# 04_MOSFET.net
KiCad netlist of a schematic drawn in Altium Designer
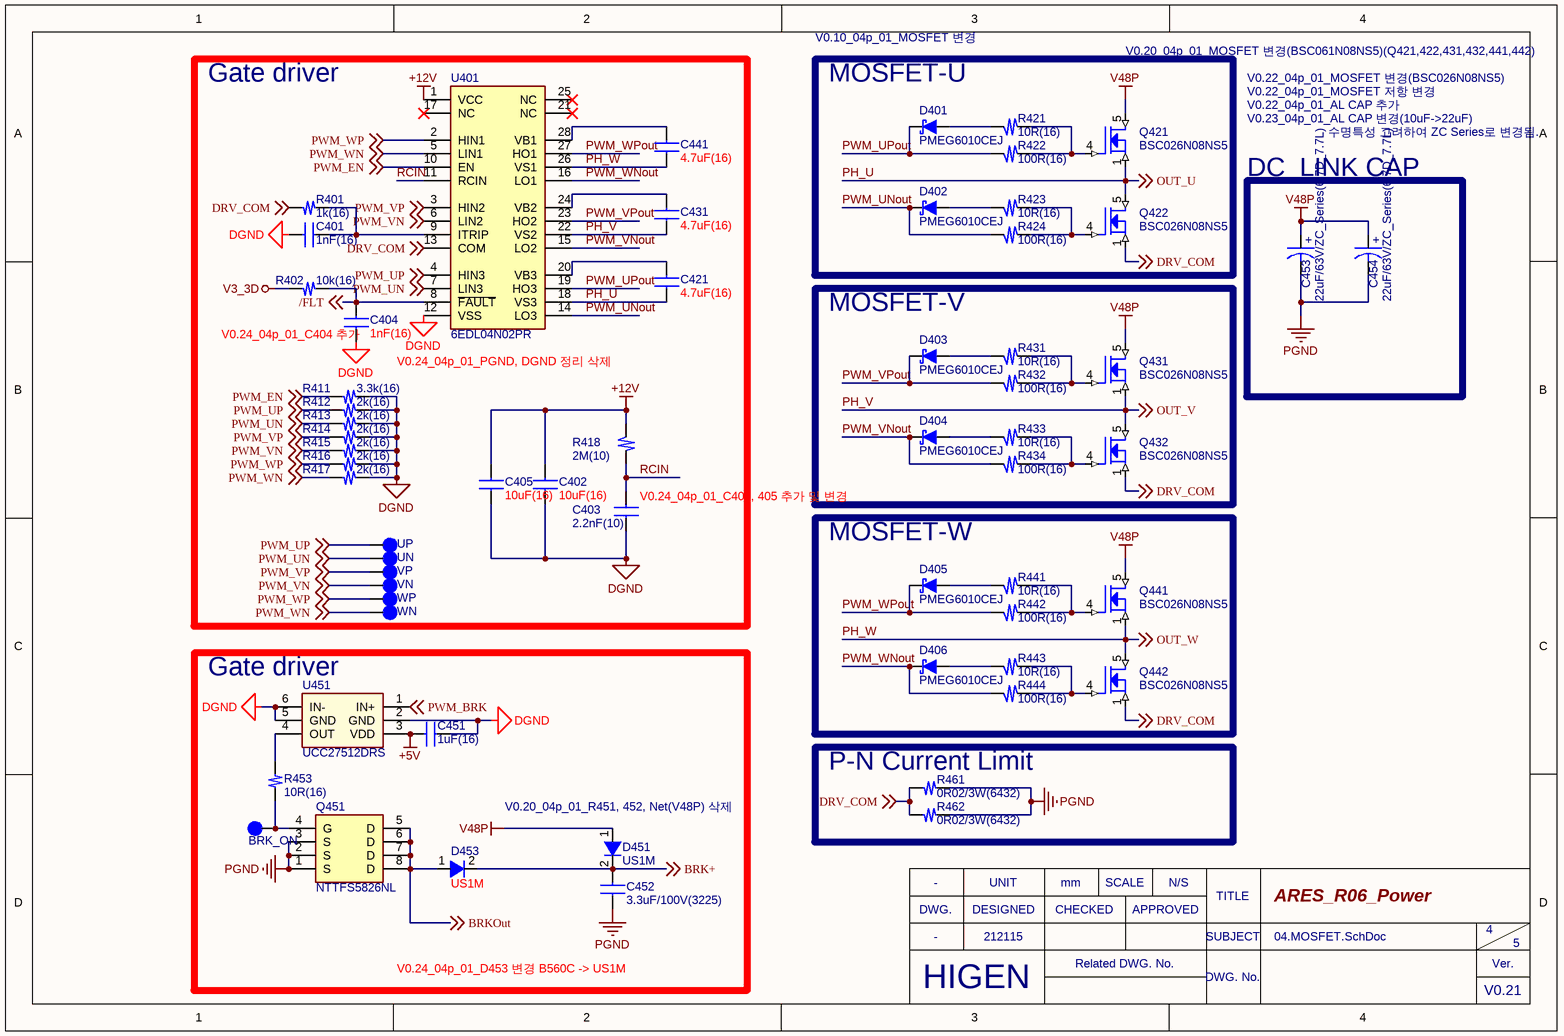
[diagram p0: 04.MOSFET.SchDoc]

(export (version "E")
  (design (tool "Eeschema 10.0.6"))
  (components
    (comp (ref "BRK_ON")
      (value "TP")
      (footprint "TP-SMD")
      (fields (field (name "MFR") "Keystone Electronics") (field (name "TIINTPARTNUMBER") "2H0026"))
      (libsource (lib "*") (part "2H_TestPointThroughHole"))
    )
    (comp (ref "C401")
      (value "1nF(16)")
      (footprint "C-1608S")
      (libsource (lib "AM437X_MAIN_LOW") (part "Cap_NP"))
    )
    (comp (ref "C402") (value "10uF(16)") (footprint "C-1608S") (libsource (lib "HIGEN") (part "Cap_NP")))
    (comp (ref "C403") (value "2.2nF(10)") (footprint "C-1005S") (libsource (lib "HIGEN") (part "Cap_NP")))
    (comp (ref "C404")
      (value "1nF(16)")
      (footprint "C-1608S")
      (libsource (lib "AM437X_MAIN_LOW") (part "Cap_NP"))
    )
    (comp (ref "C405") (value "10uF(16)") (footprint "C-1608S") (libsource (lib "HIGEN") (part "Cap_NP")))
    (comp (ref "C421") (value "4.7uF(16)") (footprint "C-1608S") (libsource (lib "HIGEN") (part "Cap_NP")))
    (comp (ref "C431") (value "4.7uF(16)") (footprint "C-1608S") (libsource (lib "HIGEN") (part "Cap_NP")))
    (comp (ref "C441") (value "4.7uF(16)") (footprint "C-1608S") (libsource (lib "HIGEN") (part "Cap_NP")))
    (comp (ref "C451")
      (value "1uF(16)")
      (footprint "C-1608S")
      (libsource (lib "AM437X_MAIN_LOW") (part "Cap_NP"))
    )
    (comp (ref "C452")
      (value "3.3uF/100V(3225)")
      (footprint "C-3225")
      (libsource (lib "HIGEN") (part "Cap_NP"))
    )
    (comp (ref "C453")
      (value "22uF/63V/ZC_Series(6.7D_7.7L)")
      (footprint "EC-F80")
      (libsource (lib "HIGEN") (part "CAP_Pol"))
    )
    (comp (ref "C454")
      (value "22uF/63V/ZC_Series(6.7D_7.7L)")
      (footprint "EC-F80")
      (libsource (lib "HIGEN") (part "CAP_Pol"))
    )
    (comp (ref "D401")
      (value "PMEG6010CEJ")
      (footprint "SOD-323")
      (libsource (lib "HIGEN") (part "Diode_schottky"))
    )
    (comp (ref "D402")
      (value "PMEG6010CEJ")
      (footprint "SOD-323")
      (libsource (lib "HIGEN") (part "Diode_schottky"))
    )
    (comp (ref "D403")
      (value "PMEG6010CEJ")
      (footprint "SOD-323")
      (libsource (lib "HIGEN") (part "Diode_schottky"))
    )
    (comp (ref "D404")
      (value "PMEG6010CEJ")
      (footprint "SOD-323")
      (libsource (lib "HIGEN") (part "Diode_schottky"))
    )
    (comp (ref "D405")
      (value "PMEG6010CEJ")
      (footprint "SOD-323")
      (libsource (lib "HIGEN") (part "Diode_schottky"))
    )
    (comp (ref "D406")
      (value "PMEG6010CEJ")
      (footprint "SOD-323")
      (libsource (lib "HIGEN") (part "Diode_schottky"))
    )
    (comp (ref "D451") (value "US1M") (footprint "SMA") (libsource (lib "HIGEN") (part "Diode")))
    (comp (ref "D453") (value "US1M") (footprint "SMA") (libsource (lib "HIGEN") (part "Diode")))
    (comp (ref "Q421")
      (value "BSC026N08NS5")
      (footprint "PG-TDSON-8 FL")
      (libsource (lib "*") (part "MOSFET N"))
    )
    (comp (ref "Q422")
      (value "BSC026N08NS5")
      (footprint "PG-TDSON-8 FL")
      (libsource (lib "*") (part "MOSFET N"))
    )
    (comp (ref "Q431")
      (value "BSC026N08NS5")
      (footprint "PG-TDSON-8 FL")
      (libsource (lib "*") (part "MOSFET N"))
    )
    (comp (ref "Q432")
      (value "BSC026N08NS5")
      (footprint "PG-TDSON-8 FL")
      (libsource (lib "*") (part "MOSFET N"))
    )
    (comp (ref "Q441")
      (value "BSC026N08NS5")
      (footprint "PG-TDSON-8 FL")
      (libsource (lib "*") (part "MOSFET N"))
    )
    (comp (ref "Q442")
      (value "BSC026N08NS5")
      (footprint "PG-TDSON-8 FL")
      (libsource (lib "*") (part "MOSFET N"))
    )
    (comp (ref "Q451")
      (value "NTTFS5826NL")
      (footprint "WDFN-8")
      (libsource (lib "HIGEN") (part "NTTFS5826NL"))
    )
    (comp (ref "R401") (value "1k(16)") (footprint "R-1608") (libsource (lib "HIGEN") (part "Res")))
    (comp (ref "R402") (value "10k(16)") (footprint "R-1608S") (libsource (lib "HIGEN") (part "Res")))
    (comp (ref "R411") (value "3.3k(16)") (footprint "R-1608S") (libsource (lib "HIGEN") (part "Res")))
    (comp (ref "R412") (value "2k(16)") (footprint "R-1608S") (libsource (lib "HIGEN") (part "Res")))
    (comp (ref "R413") (value "2k(16)") (footprint "R-1608S") (libsource (lib "HIGEN") (part "Res")))
    (comp (ref "R414") (value "2k(16)") (footprint "R-1608S") (libsource (lib "HIGEN") (part "Res")))
    (comp (ref "R415") (value "2k(16)") (footprint "R-1608S") (libsource (lib "HIGEN") (part "Res")))
    (comp (ref "R416") (value "2k(16)") (footprint "R-1608S") (libsource (lib "HIGEN") (part "Res")))
    (comp (ref "R417") (value "2k(16)") (footprint "R-1608S") (libsource (lib "HIGEN") (part "Res")))
    (comp (ref "R418")
      (value "2M(10)")
      (footprint "R-1005S")
      (libsource (lib "AM437X_MAIN_LOW") (part "Res"))
    )
    (comp (ref "R421") (value "10R(16)") (footprint "R-1608S") (libsource (lib "") (part "Res_1")))
    (comp (ref "R422") (value "100R(16)") (footprint "R-1608S") (libsource (lib "") (part "Res_1")))
    (comp (ref "R423") (value "10R(16)") (footprint "R-1608S") (libsource (lib "") (part "Res_1")))
    (comp (ref "R424") (value "100R(16)") (footprint "R-1608S") (libsource (lib "") (part "Res_1")))
    (comp (ref "R431") (value "10R(16)") (footprint "R-1608S") (libsource (lib "") (part "Res_1")))
    (comp (ref "R432") (value "100R(16)") (footprint "R-1608S") (libsource (lib "") (part "Res_1")))
    (comp (ref "R433") (value "10R(16)") (footprint "R-1608S") (libsource (lib "") (part "Res_1")))
    (comp (ref "R434") (value "100R(16)") (footprint "R-1608S") (libsource (lib "") (part "Res_1")))
    (comp (ref "R441") (value "10R(16)") (footprint "R-1608S") (libsource (lib "") (part "Res_1")))
    (comp (ref "R442") (value "100R(16)") (footprint "R-1608S") (libsource (lib "") (part "Res_1")))
    (comp (ref "R443") (value "10R(16)") (footprint "R-1608S") (libsource (lib "") (part "Res_1")))
    (comp (ref "R444") (value "100R(16)") (footprint "R-1608S") (libsource (lib "") (part "Res_1")))
    (comp (ref "R453") (value "10R(16)") (footprint "R-1608S") (libsource (lib "HIGEN") (part "Res")))
    (comp (ref "R461") (value "0R02/3W(6432)") (footprint "R-6432") (libsource (lib "HIGEN") (part "Res")))
    (comp (ref "R462") (value "0R02/3W(6432)") (footprint "R-6432") (libsource (lib "HIGEN") (part "Res")))
    (comp (ref "U401")
      (value "6EDL04N02PR")
      (footprint "TSSOP-28")
      (libsource (lib "HIGEN") (part "6EDL04N02PR"))
    )
    (comp (ref "U451")
      (value "UCC27512DRS")
      (footprint "WSON-6")
      (libsource (lib "HIGEN") (part "UCC27512DRS"))
    )
    (comp (ref "UN")
      (value "TP")
      (footprint "TP-SMD")
      (fields (field (name "MFR") "Keystone Electronics") (field (name "TIINTPARTNUMBER") "2H0026"))
      (libsource (lib "*") (part "2H_TestPointThroughHole"))
    )
    (comp (ref "UP")
      (value "TP")
      (footprint "TP-SMD")
      (fields (field (name "MFR") "Keystone Electronics") (field (name "TIINTPARTNUMBER") "2H0026"))
      (libsource (lib "*") (part "2H_TestPointThroughHole"))
    )
    (comp (ref "VN")
      (value "TP")
      (footprint "TP-SMD")
      (fields (field (name "MFR") "Keystone Electronics") (field (name "TIINTPARTNUMBER") "2H0026"))
      (libsource (lib "*") (part "2H_TestPointThroughHole"))
    )
    (comp (ref "VP")
      (value "TP")
      (footprint "TP-SMD")
      (fields (field (name "MFR") "Keystone Electronics") (field (name "TIINTPARTNUMBER") "2H0026"))
      (libsource (lib "*") (part "2H_TestPointThroughHole"))
    )
    (comp (ref "WN")
      (value "TP")
      (footprint "TP-SMD")
      (fields (field (name "MFR") "Keystone Electronics") (field (name "TIINTPARTNUMBER") "2H0026"))
      (libsource (lib "*") (part "2H_TestPointThroughHole"))
    )
    (comp (ref "WP")
      (value "TP")
      (footprint "TP-SMD")
      (fields (field (name "MFR") "Keystone Electronics") (field (name "TIINTPARTNUMBER") "2H0026"))
      (libsource (lib "*") (part "2H_TestPointThroughHole"))
    )
  )
  (nets
    (net (code "1") (name "+5V") (class "Default")
      (node (ref "C451") (pin "1") (pinfunction "1_1") (pintype "passive"))
      (node (ref "U451") (pin "3") (pinfunction "VDD_3") (pintype "passive"))
    )
    (net (code "2") (name "+12V") (class "Default")
      (node (ref "C402") (pin "1") (pinfunction "1_1") (pintype "passive"))
      (node (ref "C405") (pin "1") (pinfunction "1_1") (pintype "passive"))
      (node (ref "R418") (pin "2") (pinfunction "2_2") (pintype "passive"))
      (node (ref "U401") (pin "1") (pinfunction "VCC_1") (pintype "passive"))
    )
    (net (code "3") (name "/PWM_UNout") (class "Default")
      (node (ref "D402") (pin "2") (pinfunction "K_2") (pintype "passive"))
      (node (ref "R424") (pin "2") (pinfunction "2_2") (pintype "passive"))
      (node (ref "U401") (pin "14") (pinfunction "LO3_14") (pintype "passive"))
    )
    (net (code "4") (name "/PWM_UPout") (class "Default")
      (node (ref "D401") (pin "2") (pinfunction "K_2") (pintype "passive"))
      (node (ref "R422") (pin "2") (pinfunction "2_2") (pintype "passive"))
      (node (ref "U401") (pin "19") (pinfunction "HO3_19") (pintype "passive"))
    )
    (net (code "5") (name "/PWM_VNout") (class "Default")
      (node (ref "D404") (pin "2") (pinfunction "K_2") (pintype "passive"))
      (node (ref "R434") (pin "2") (pinfunction "2_2") (pintype "passive"))
      (node (ref "U401") (pin "15") (pinfunction "LO2_15") (pintype "passive"))
    )
    (net (code "6") (name "/PWM_VPout") (class "Default")
      (node (ref "D403") (pin "2") (pinfunction "K_2") (pintype "passive"))
      (node (ref "R432") (pin "2") (pinfunction "2_2") (pintype "passive"))
      (node (ref "U401") (pin "23") (pinfunction "HO2_23") (pintype "passive"))
    )
    (net (code "7") (name "/PWM_WNout") (class "Default")
      (node (ref "D406") (pin "2") (pinfunction "K_2") (pintype "passive"))
      (node (ref "R444") (pin "2") (pinfunction "2_2") (pintype "passive"))
      (node (ref "U401") (pin "16") (pinfunction "LO1_16") (pintype "passive"))
    )
    (net (code "8") (name "/PWM_WPout") (class "Default")
      (node (ref "D405") (pin "2") (pinfunction "K_2") (pintype "passive"))
      (node (ref "R442") (pin "2") (pinfunction "2_2") (pintype "passive"))
      (node (ref "U401") (pin "27") (pinfunction "HO1_27") (pintype "passive"))
    )
    (net (code "9") (name "/RCIN") (class "Default")
      (node (ref "C403") (pin "2") (pinfunction "2_2") (pintype "passive"))
      (node (ref "R418") (pin "1") (pinfunction "1_1") (pintype "passive"))
      (node (ref "U401") (pin "11") (pinfunction "RCIN_11") (pintype "passive"))
    )
    (net (code "10") (name "BRK+") (class "Default")
      (node (ref "C452") (pin "2") (pinfunction "2_2") (pintype "passive"))
      (node (ref "D451") (pin "2") (pinfunction "K_2") (pintype "passive"))
      (node (ref "D453") (pin "2") (pinfunction "K_2") (pintype "passive"))
    )
    (net (code "11") (name "BRKOut") (class "Default")
      (node (ref "D453") (pin "1") (pinfunction "A_1") (pintype "passive"))
      (node (ref "Q451") (pin "5") (pinfunction "D_5") (pintype "passive"))
      (node (ref "Q451") (pin "6") (pinfunction "D_6") (pintype "passive"))
      (node (ref "Q451") (pin "7") (pinfunction "D_7") (pintype "passive"))
      (node (ref "Q451") (pin "8") (pinfunction "D_8") (pintype "passive"))
    )
    (net (code "12") (name "DGND") (class "Default")
      (node (ref "C401") (pin "1") (pinfunction "1_1") (pintype "passive"))
      (node (ref "C402") (pin "2") (pinfunction "2_2") (pintype "passive"))
      (node (ref "C403") (pin "1") (pinfunction "1_1") (pintype "passive"))
      (node (ref "C404") (pin "1") (pinfunction "1_1") (pintype "passive"))
      (node (ref "C405") (pin "2") (pinfunction "2_2") (pintype "passive"))
      (node (ref "C451") (pin "2") (pinfunction "2_2") (pintype "passive"))
      (node (ref "R411") (pin "2") (pinfunction "P2_2") (pintype "passive"))
      (node (ref "R412") (pin "1") (pinfunction "P1_1") (pintype "passive"))
      (node (ref "R413") (pin "1") (pinfunction "P1_1") (pintype "passive"))
      (node (ref "R414") (pin "1") (pinfunction "P1_1") (pintype "passive"))
      (node (ref "R415") (pin "1") (pinfunction "P1_1") (pintype "passive"))
      (node (ref "R416") (pin "2") (pinfunction "P2_2") (pintype "passive"))
      (node (ref "R417") (pin "2") (pinfunction "P2_2") (pintype "passive"))
      (node (ref "U401") (pin "12") (pinfunction "VSS_12") (pintype "passive"))
      (node (ref "U451") (pin "2") (pinfunction "GND_2") (pintype "passive"))
      (node (ref "U451") (pin "5") (pinfunction "GND_5") (pintype "passive"))
      (node (ref "U451") (pin "6") (pinfunction "IN-_6") (pintype "passive"))
    )
    (net (code "13") (name "DRV_COM") (class "Default")
      (node (ref "Q422") (pin "1") (pinfunction "SOURCE_1") (pintype "input"))
      (node (ref "Q432") (pin "1") (pinfunction "SOURCE_1") (pintype "input"))
      (node (ref "Q442") (pin "1") (pinfunction "SOURCE_1") (pintype "input"))
      (node (ref "R401") (pin "1") (pinfunction "P1_1") (pintype "passive"))
      (node (ref "R461") (pin "2") (pinfunction "P2_2") (pintype "passive"))
      (node (ref "R462") (pin "2") (pinfunction "P2_2") (pintype "passive"))
      (node (ref "U401") (pin "13") (pinfunction "COM_13") (pintype "passive"))
    )
    (net (code "14") (name "Net-(D401-A)") (class "Default")
      (node (ref "D401") (pin "1") (pinfunction "A_1") (pintype "passive"))
      (node (ref "R421") (pin "2") (pinfunction "2_2") (pintype "passive"))
    )
    (net (code "15") (name "Net-(D402-A)") (class "Default")
      (node (ref "D402") (pin "1") (pinfunction "A_1") (pintype "passive"))
      (node (ref "R423") (pin "2") (pinfunction "2_2") (pintype "passive"))
    )
    (net (code "16") (name "Net-(D403-A)") (class "Default")
      (node (ref "D403") (pin "1") (pinfunction "A_1") (pintype "passive"))
      (node (ref "R431") (pin "2") (pinfunction "2_2") (pintype "passive"))
    )
    (net (code "17") (name "Net-(D404-A)") (class "Default")
      (node (ref "D404") (pin "1") (pinfunction "A_1") (pintype "passive"))
      (node (ref "R433") (pin "2") (pinfunction "2_2") (pintype "passive"))
    )
    (net (code "18") (name "Net-(D405-A)") (class "Default")
      (node (ref "D405") (pin "1") (pinfunction "A_1") (pintype "passive"))
      (node (ref "R441") (pin "2") (pinfunction "2_2") (pintype "passive"))
    )
    (net (code "19") (name "Net-(D406-A)") (class "Default")
      (node (ref "D406") (pin "1") (pinfunction "A_1") (pintype "passive"))
      (node (ref "R443") (pin "2") (pinfunction "2_2") (pintype "passive"))
    )
    (net (code "20") (name "Net-(Q421-GATE)") (class "Default")
      (node (ref "Q421") (pin "4") (pinfunction "GATE_4") (pintype "input"))
      (node (ref "R421") (pin "1") (pinfunction "1_1") (pintype "passive"))
      (node (ref "R422") (pin "1") (pinfunction "1_1") (pintype "passive"))
    )
    (net (code "21") (name "Net-(Q422-GATE)") (class "Default")
      (node (ref "Q422") (pin "4") (pinfunction "GATE_4") (pintype "input"))
      (node (ref "R423") (pin "1") (pinfunction "1_1") (pintype "passive"))
      (node (ref "R424") (pin "1") (pinfunction "1_1") (pintype "passive"))
    )
    (net (code "22") (name "Net-(Q431-GATE)") (class "Default")
      (node (ref "Q431") (pin "4") (pinfunction "GATE_4") (pintype "input"))
      (node (ref "R431") (pin "1") (pinfunction "1_1") (pintype "passive"))
      (node (ref "R432") (pin "1") (pinfunction "1_1") (pintype "passive"))
    )
    (net (code "23") (name "Net-(Q432-GATE)") (class "Default")
      (node (ref "Q432") (pin "4") (pinfunction "GATE_4") (pintype "input"))
      (node (ref "R433") (pin "1") (pinfunction "1_1") (pintype "passive"))
      (node (ref "R434") (pin "1") (pinfunction "1_1") (pintype "passive"))
    )
    (net (code "24") (name "Net-(Q441-GATE)") (class "Default")
      (node (ref "Q441") (pin "4") (pinfunction "GATE_4") (pintype "input"))
      (node (ref "R441") (pin "1") (pinfunction "1_1") (pintype "passive"))
      (node (ref "R442") (pin "1") (pinfunction "1_1") (pintype "passive"))
    )
    (net (code "25") (name "Net-(Q442-GATE)") (class "Default")
      (node (ref "Q442") (pin "4") (pinfunction "GATE_4") (pintype "input"))
      (node (ref "R443") (pin "1") (pinfunction "1_1") (pintype "passive"))
      (node (ref "R444") (pin "1") (pinfunction "1_1") (pintype "passive"))
    )
    (net (code "26") (name "Net-(Q451-G)") (class "Default")
      (node (ref "BRK_ON") (pin "1") (pinfunction "1_1") (pintype "passive"))
      (node (ref "Q451") (pin "4") (pinfunction "G_4") (pintype "passive"))
      (node (ref "R453") (pin "1") (pinfunction "P1_1") (pintype "passive"))
    )
    (net (code "27") (name "Net-(R401-P2)") (class "Default")
      (node (ref "C401") (pin "2") (pinfunction "2_2") (pintype "passive"))
      (node (ref "R401") (pin "2") (pinfunction "P2_2") (pintype "passive"))
      (node (ref "U401") (pin "9") (pinfunction "ITRIP_9") (pintype "passive"))
    )
    (net (code "28") (name "Net-(R453-P2)") (class "Default")
      (node (ref "R453") (pin "2") (pinfunction "P2_2") (pintype "passive"))
      (node (ref "U451") (pin "4") (pinfunction "OUT_4") (pintype "passive"))
    )
    (net (code "29") (name "Net-(U401-VB1)") (class "Default")
      (node (ref "C441") (pin "2") (pinfunction "2_2") (pintype "passive"))
      (node (ref "U401") (pin "28") (pinfunction "VB1_28") (pintype "passive"))
    )
    (net (code "30") (name "Net-(U401-VB2)") (class "Default")
      (node (ref "C431") (pin "2") (pinfunction "2_2") (pintype "passive"))
      (node (ref "U401") (pin "24") (pinfunction "VB2_24") (pintype "passive"))
    )
    (net (code "31") (name "Net-(U401-VB3)") (class "Default")
      (node (ref "C421") (pin "1") (pinfunction "1_1") (pintype "passive"))
      (node (ref "U401") (pin "20") (pinfunction "VB3_20") (pintype "passive"))
    )
    (net (code "32") (name "OUT_U") (class "Default")
      (node (ref "C421") (pin "2") (pinfunction "2_2") (pintype "passive"))
      (node (ref "Q421") (pin "1") (pinfunction "SOURCE_1") (pintype "input"))
      (node (ref "Q422") (pin "5") (pinfunction "DRAIN_5") (pintype "input"))
      (node (ref "U401") (pin "18") (pinfunction "VS3_18") (pintype "passive"))
    )
    (net (code "33") (name "OUT_V") (class "Default")
      (node (ref "C431") (pin "1") (pinfunction "1_1") (pintype "passive"))
      (node (ref "Q431") (pin "1") (pinfunction "SOURCE_1") (pintype "input"))
      (node (ref "Q432") (pin "5") (pinfunction "DRAIN_5") (pintype "input"))
      (node (ref "U401") (pin "22") (pinfunction "VS2_22") (pintype "passive"))
    )
    (net (code "34") (name "OUT_W") (class "Default")
      (node (ref "C441") (pin "1") (pinfunction "1_1") (pintype "passive"))
      (node (ref "Q441") (pin "1") (pinfunction "SOURCE_1") (pintype "input"))
      (node (ref "Q442") (pin "5") (pinfunction "DRAIN_5") (pintype "input"))
      (node (ref "U401") (pin "26") (pinfunction "VS1_26") (pintype "passive"))
    )
    (net (code "35") (name "PGND") (class "Default")
      (node (ref "C452") (pin "1") (pinfunction "1_1") (pintype "passive"))
      (node (ref "C453") (pin "2") (pinfunction "2_2") (pintype "passive"))
      (node (ref "C454") (pin "2") (pinfunction "2_2") (pintype "passive"))
      (node (ref "Q451") (pin "1") (pinfunction "S_1") (pintype "passive"))
      (node (ref "Q451") (pin "2") (pinfunction "S_2") (pintype "passive"))
      (node (ref "Q451") (pin "3") (pinfunction "S_3") (pintype "passive"))
      (node (ref "R461") (pin "1") (pinfunction "P1_1") (pintype "passive"))
      (node (ref "R462") (pin "1") (pinfunction "P1_1") (pintype "passive"))
    )
    (net (code "36") (name "PWM_BRK") (class "Default")
      (node (ref "U451") (pin "1") (pinfunction "IN+_1") (pintype "passive"))
    )
    (net (code "37") (name "PWM_EN") (class "Default")
      (node (ref "R411") (pin "1") (pinfunction "P1_1") (pintype "passive"))
      (node (ref "U401") (pin "10") (pinfunction "EN_10") (pintype "passive"))
    )
    (net (code "38") (name "PWM_UN") (class "Default")
      (node (ref "R413") (pin "2") (pinfunction "P2_2") (pintype "passive"))
      (node (ref "U401") (pin "7") (pinfunction "LIN3_7") (pintype "passive"))
      (node (ref "UN") (pin "1") (pinfunction "1_1") (pintype "passive"))
    )
    (net (code "39") (name "PWM_UP") (class "Default")
      (node (ref "R412") (pin "2") (pinfunction "P2_2") (pintype "passive"))
      (node (ref "U401") (pin "4") (pinfunction "HIN3_4") (pintype "passive"))
      (node (ref "UP") (pin "1") (pinfunction "1_1") (pintype "passive"))
    )
    (net (code "40") (name "PWM_VN") (class "Default")
      (node (ref "R415") (pin "2") (pinfunction "P2_2") (pintype "passive"))
      (node (ref "U401") (pin "6") (pinfunction "LIN2_6") (pintype "passive"))
      (node (ref "VN") (pin "1") (pinfunction "1_1") (pintype "passive"))
    )
    (net (code "41") (name "PWM_VP") (class "Default")
      (node (ref "R414") (pin "2") (pinfunction "P2_2") (pintype "passive"))
      (node (ref "U401") (pin "3") (pinfunction "HIN2_3") (pintype "passive"))
      (node (ref "VP") (pin "1") (pinfunction "1_1") (pintype "passive"))
    )
    (net (code "42") (name "PWM_WN") (class "Default")
      (node (ref "R417") (pin "1") (pinfunction "P1_1") (pintype "passive"))
      (node (ref "U401") (pin "5") (pinfunction "LIN1_5") (pintype "passive"))
      (node (ref "WN") (pin "1") (pinfunction "1_1") (pintype "passive"))
    )
    (net (code "43") (name "PWM_WP") (class "Default")
      (node (ref "R416") (pin "1") (pinfunction "P1_1") (pintype "passive"))
      (node (ref "U401") (pin "2") (pinfunction "HIN1_2") (pintype "passive"))
      (node (ref "WP") (pin "1") (pinfunction "1_1") (pintype "passive"))
    )
    (net (code "44") (name "V3_3D") (class "Default")
      (node (ref "R402") (pin "1") (pinfunction "P1_1") (pintype "passive"))
    )
    (net (code "45") (name "V48P") (class "Default")
      (node (ref "C453") (pin "1") (pinfunction "1_1") (pintype "passive"))
      (node (ref "C454") (pin "1") (pinfunction "1_1") (pintype "passive"))
      (node (ref "D451") (pin "1") (pinfunction "A_1") (pintype "passive"))
      (node (ref "Q421") (pin "5") (pinfunction "DRAIN_5") (pintype "input"))
      (node (ref "Q431") (pin "5") (pinfunction "DRAIN_5") (pintype "input"))
      (node (ref "Q441") (pin "5") (pinfunction "DRAIN_5") (pintype "input"))
    )
    (net (code "46") (name "unconnected-(U401-NC-Pad17)") (class "Default")
      (node (ref "U401") (pin "17") (pinfunction "NC_17") (pintype "passive+no_connect"))
    )
    (net (code "47") (name "unconnected-(U401-NC-Pad21)") (class "Default")
      (node (ref "U401") (pin "21") (pinfunction "NC_21") (pintype "passive+no_connect"))
    )
    (net (code "48") (name "unconnected-(U401-NC-Pad25)") (class "Default")
      (node (ref "U401") (pin "25") (pinfunction "NC_25") (pintype "passive+no_connect"))
    )
    (net (code "49") (name "{slash}FLT") (class "Default")
      (node (ref "C404") (pin "2") (pinfunction "2_2") (pintype "passive"))
      (node (ref "R402") (pin "2") (pinfunction "P2_2") (pintype "passive"))
      (node (ref "U401") (pin "8") (pinfunction "~{FAULT}_8") (pintype "passive"))
    )
  )
)
